# easyeda-schematic.net
KiCad netlist of a schematic drawn in EasyEDA
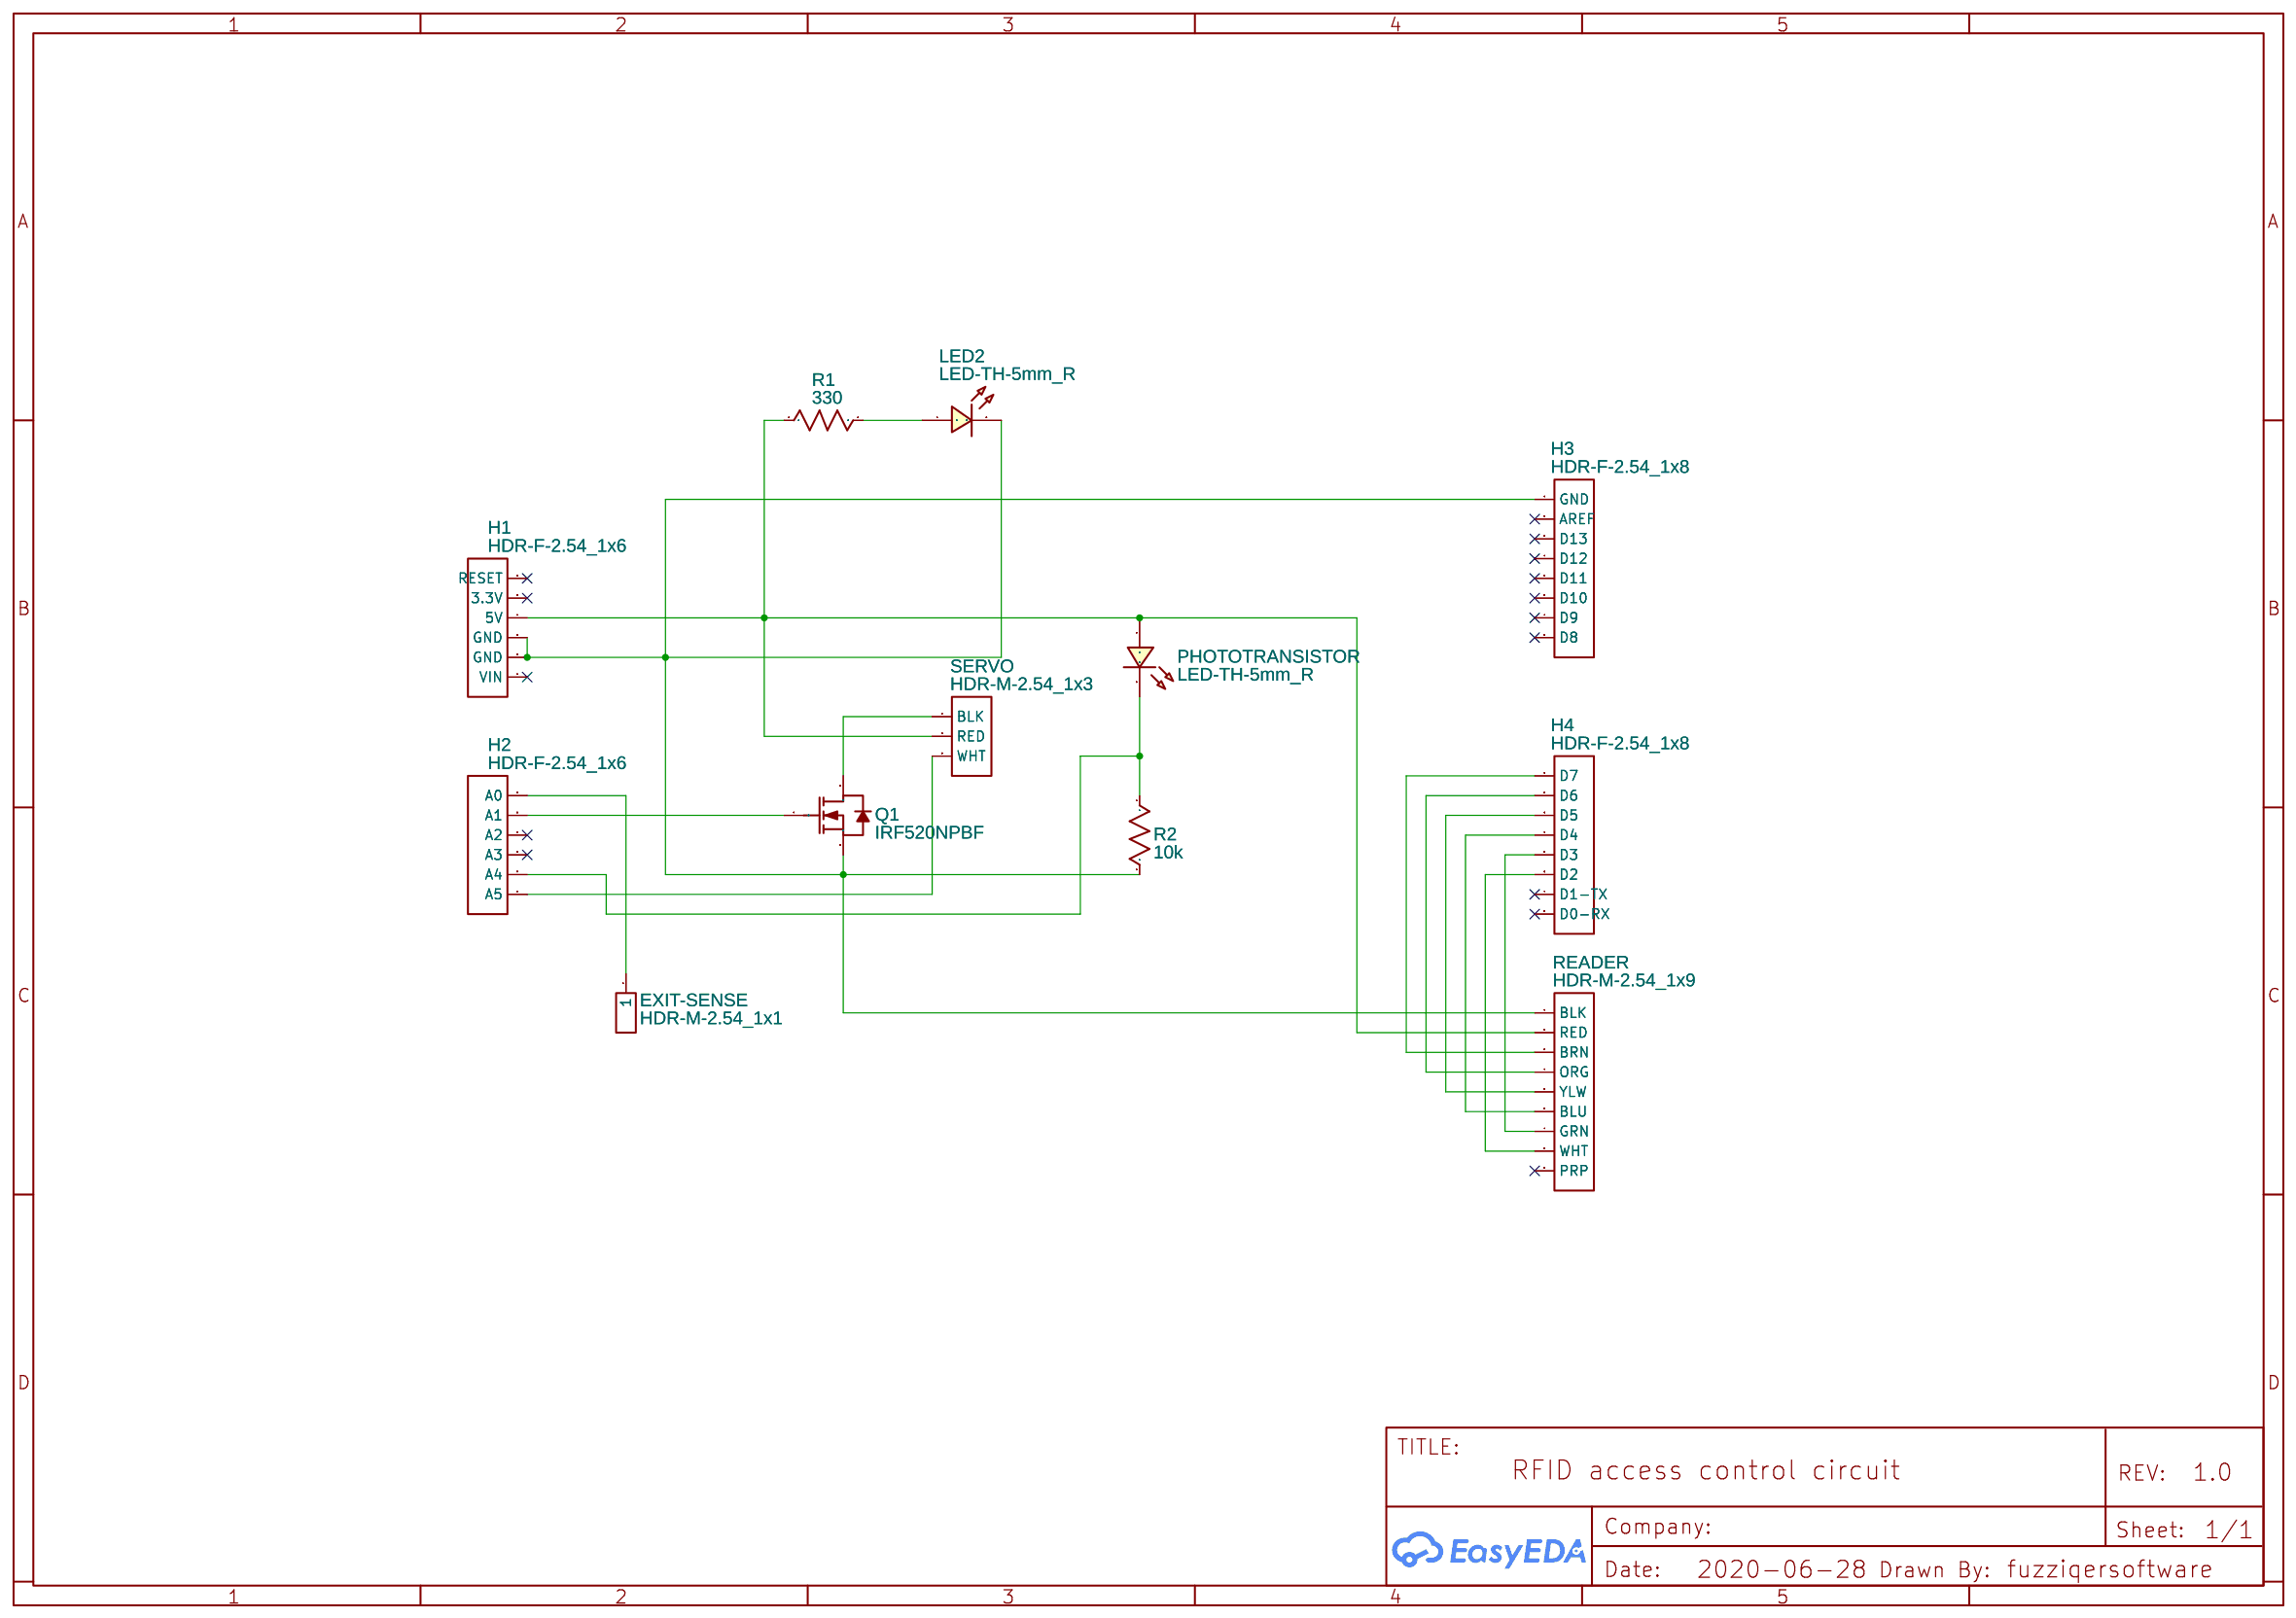
[diagram p0: schematic sheet]

(export (version "E")
  (design (tool "Eeschema 10.0.6"))
  (components
    (comp (ref "EXIT-SENSE")
      (value "HDR-M-2.54_1x1")
      (fields (field (name "BOM_Supplier Part") "C81276"))
      (libsource (lib "") (part "HDR-M-2.54_1x1"))
    )
    (comp (ref "H1")
      (value "HDR-F-2.54_1x6")
      (fields (field (name "BOM_Supplier Part") "C40877"))
      (libsource (lib "") (part "HDR-F-2.54_1x6"))
    )
    (comp (ref "H2")
      (value "HDR-F-2.54_1x6")
      (fields (field (name "BOM_Supplier Part") "C40877"))
      (libsource (lib "") (part "HDR-F-2.54_1x6_1"))
    )
    (comp (ref "H3")
      (value "HDR-F-2.54_1x8")
      (fields (field (name "BOM_Supplier Part") "C225505"))
      (libsource (lib "") (part "HDR-F-2.54_1x8"))
    )
    (comp (ref "H4")
      (value "HDR-F-2.54_1x8")
      (fields (field (name "BOM_Supplier Part") "C225505"))
      (libsource (lib "") (part "HDR-F-2.54_1x8_1"))
    )
    (comp (ref "LED2")
      (value "LED-TH-5mm_R")
      (fields
        (field (name "BOM_Manufacturer Part") "333-2SURD/S530-A3")
        (field (name "BOM_Supplier Part") "C87271")
      )
      (libsource (lib "") (part "LED-TH-5mm_R"))
    )
    (comp (ref "PHOTOTRANSISTOR")
      (value "LED-TH-5mm_R")
      (fields
        (field (name "BOM_Manufacturer Part") "333-2SURD/S530-A3")
        (field (name "BOM_Supplier Part") "C87271")
      )
      (libsource (lib "") (part "LED-TH-5mm_R_1"))
    )
    (comp (ref "Q1")
      (value "IRF520NPBF")
      (fields (field (name "BOM_Supplier Part") "C2598"))
      (libsource (lib "") (part "IRF520NPBF"))
    )
    (comp (ref "R1") (value "330") (libsource (lib "") (part "R_AXIAL-0.4_US")))
    (comp (ref "R2") (value "10k") (libsource (lib "") (part "R_AXIAL-0.4_US_1")))
    (comp (ref "READER")
      (value "HDR-M-2.54_1x9")
      (fields (field (name "BOM_Supplier Part") "C225484"))
      (libsource (lib "") (part "HDR-M-2.54_1x9"))
    )
    (comp (ref "SERVO")
      (value "HDR-M-2.54_1x3")
      (fields (field (name "BOM_Supplier Part") "C180248"))
      (libsource (lib "") (part "HDR-M-2.54_1x3"))
    )
  )
  (nets
    (net (code "1") (name "Net-(H1-5V)") (class "Default")
      (node (ref "H1") (pin "4") (pinfunction "5V_4") (pintype "input"))
      (node (ref "PHOTOTRANSISTOR") (pin "1") (pinfunction "1_1") (pintype "unspecified"))
      (node (ref "R1") (pin "1") (pinfunction "1_1") (pintype "unspecified"))
      (node (ref "READER") (pin "2") (pinfunction "RED_2") (pintype "unspecified"))
      (node (ref "SERVO") (pin "2") (pinfunction "RED_2") (pintype "input"))
    )
    (net (code "2") (name "Net-(H2-A0)") (class "Default")
      (node (ref "EXIT-SENSE") (pin "1") (pinfunction "1_1") (pintype "input"))
      (node (ref "H2") (pin "6") (pinfunction "A0_6") (pintype "input"))
    )
    (net (code "3") (name "Net-(H2-A1)") (class "Default")
      (node (ref "H2") (pin "5") (pinfunction "A1_5") (pintype "input"))
      (node (ref "Q1") (pin "1") (pinfunction "G_1") (pintype "unspecified"))
    )
    (net (code "4") (name "Net-(H2-A4)") (class "Default")
      (node (ref "H2") (pin "2") (pinfunction "A4_2") (pintype "input"))
      (node (ref "PHOTOTRANSISTOR") (pin "2") (pinfunction "2_2") (pintype "unspecified"))
      (node (ref "R2") (pin "1") (pinfunction "1_1") (pintype "unspecified"))
    )
    (net (code "5") (name "Net-(H2-A5)") (class "Default")
      (node (ref "H2") (pin "1") (pinfunction "A5_1") (pintype "input"))
      (node (ref "SERVO") (pin "3") (pinfunction "WHT_3") (pintype "input"))
    )
    (net (code "6") (name "Net-(H3-GND)") (class "Default")
      (node (ref "H1") (pin "2") (pinfunction "GND_2") (pintype "input"))
      (node (ref "H1") (pin "3") (pinfunction "GND_3") (pintype "input"))
      (node (ref "H3") (pin "1") (pinfunction "GND_1") (pintype "unspecified"))
      (node (ref "LED2") (pin "2") (pinfunction "2_2") (pintype "unspecified"))
      (node (ref "Q1") (pin "3") (pinfunction "S_3") (pintype "unspecified"))
      (node (ref "R2") (pin "2") (pinfunction "2_2") (pintype "unspecified"))
      (node (ref "READER") (pin "1") (pinfunction "BLK_1") (pintype "unspecified"))
    )
    (net (code "7") (name "Net-(H4-D2)") (class "Default")
      (node (ref "H4") (pin "6") (pinfunction "D2_6") (pintype "unspecified"))
      (node (ref "READER") (pin "8") (pinfunction "WHT_8") (pintype "unspecified"))
    )
    (net (code "8") (name "Net-(H4-D3)") (class "Default")
      (node (ref "H4") (pin "5") (pinfunction "D3_5") (pintype "unspecified"))
      (node (ref "READER") (pin "7") (pinfunction "GRN_7") (pintype "unspecified"))
    )
    (net (code "9") (name "Net-(H4-D4)") (class "Default")
      (node (ref "H4") (pin "4") (pinfunction "D4_4") (pintype "unspecified"))
      (node (ref "READER") (pin "6") (pinfunction "BLU_6") (pintype "unspecified"))
    )
    (net (code "10") (name "Net-(H4-D5)") (class "Default")
      (node (ref "H4") (pin "3") (pinfunction "D5_3") (pintype "unspecified"))
      (node (ref "READER") (pin "5") (pinfunction "YLW_5") (pintype "unspecified"))
    )
    (net (code "11") (name "Net-(H4-D6)") (class "Default")
      (node (ref "H4") (pin "2") (pinfunction "D6_2") (pintype "unspecified"))
      (node (ref "READER") (pin "4") (pinfunction "ORG_4") (pintype "unspecified"))
    )
    (net (code "12") (name "Net-(H4-D7)") (class "Default")
      (node (ref "H4") (pin "1") (pinfunction "D7_1") (pintype "unspecified"))
      (node (ref "READER") (pin "3") (pinfunction "BRN_3") (pintype "unspecified"))
    )
    (net (code "13") (name "Net-(LED2-Pad1)") (class "Default")
      (node (ref "LED2") (pin "1") (pinfunction "1_1") (pintype "unspecified"))
      (node (ref "R1") (pin "2") (pinfunction "2_2") (pintype "unspecified"))
    )
    (net (code "14") (name "Net-(Q1-D)") (class "Default")
      (node (ref "Q1") (pin "2") (pinfunction "D_2") (pintype "unspecified"))
      (node (ref "SERVO") (pin "1") (pinfunction "BLK_1") (pintype "input"))
    )
    (net (code "15") (name "unconnected-(H1-3.3V-Pad5)") (class "Default")
      (node (ref "H1") (pin "5") (pinfunction "3.3V_5") (pintype "input+no_connect"))
    )
    (net (code "16") (name "unconnected-(H1-RESET-Pad6)") (class "Default")
      (node (ref "H1") (pin "6") (pinfunction "RESET_6") (pintype "input+no_connect"))
    )
    (net (code "17") (name "unconnected-(H1-VIN-Pad1)") (class "Default")
      (node (ref "H1") (pin "1") (pinfunction "VIN_1") (pintype "input+no_connect"))
    )
    (net (code "18") (name "unconnected-(H2-A2-Pad4)") (class "Default")
      (node (ref "H2") (pin "4") (pinfunction "A2_4") (pintype "input+no_connect"))
    )
    (net (code "19") (name "unconnected-(H2-A3-Pad3)") (class "Default")
      (node (ref "H2") (pin "3") (pinfunction "A3_3") (pintype "input+no_connect"))
    )
    (net (code "20") (name "unconnected-(H3-AREF-Pad2)") (class "Default")
      (node (ref "H3") (pin "2") (pinfunction "AREF_2") (pintype "unspecified+no_connect"))
    )
    (net (code "21") (name "unconnected-(H3-D8-Pad8)") (class "Default")
      (node (ref "H3") (pin "8") (pinfunction "D8_8") (pintype "unspecified+no_connect"))
    )
    (net (code "22") (name "unconnected-(H3-D9-Pad7)") (class "Default")
      (node (ref "H3") (pin "7") (pinfunction "D9_7") (pintype "unspecified+no_connect"))
    )
    (net (code "23") (name "unconnected-(H3-D10-Pad6)") (class "Default")
      (node (ref "H3") (pin "6") (pinfunction "D10_6") (pintype "unspecified+no_connect"))
    )
    (net (code "24") (name "unconnected-(H3-D11-Pad5)") (class "Default")
      (node (ref "H3") (pin "5") (pinfunction "D11_5") (pintype "unspecified+no_connect"))
    )
    (net (code "25") (name "unconnected-(H3-D12-Pad4)") (class "Default")
      (node (ref "H3") (pin "4") (pinfunction "D12_4") (pintype "unspecified+no_connect"))
    )
    (net (code "26") (name "unconnected-(H3-D13-Pad3)") (class "Default")
      (node (ref "H3") (pin "3") (pinfunction "D13_3") (pintype "unspecified+no_connect"))
    )
    (net (code "27") (name "unconnected-(H4-D0-RX-Pad8)") (class "Default")
      (node (ref "H4") (pin "8") (pinfunction "D0-RX_8") (pintype "unspecified+no_connect"))
    )
    (net (code "28") (name "unconnected-(H4-D1-TX-Pad7)") (class "Default")
      (node (ref "H4") (pin "7") (pinfunction "D1-TX_7") (pintype "unspecified+no_connect"))
    )
    (net (code "29") (name "unconnected-(READER-PRP-Pad9)") (class "Default")
      (node (ref "READER") (pin "9") (pinfunction "PRP_9") (pintype "unspecified+no_connect"))
    )
  )
)
